# ISS-Notify.net
KiCad netlist of a schematic drawn in EAGLE
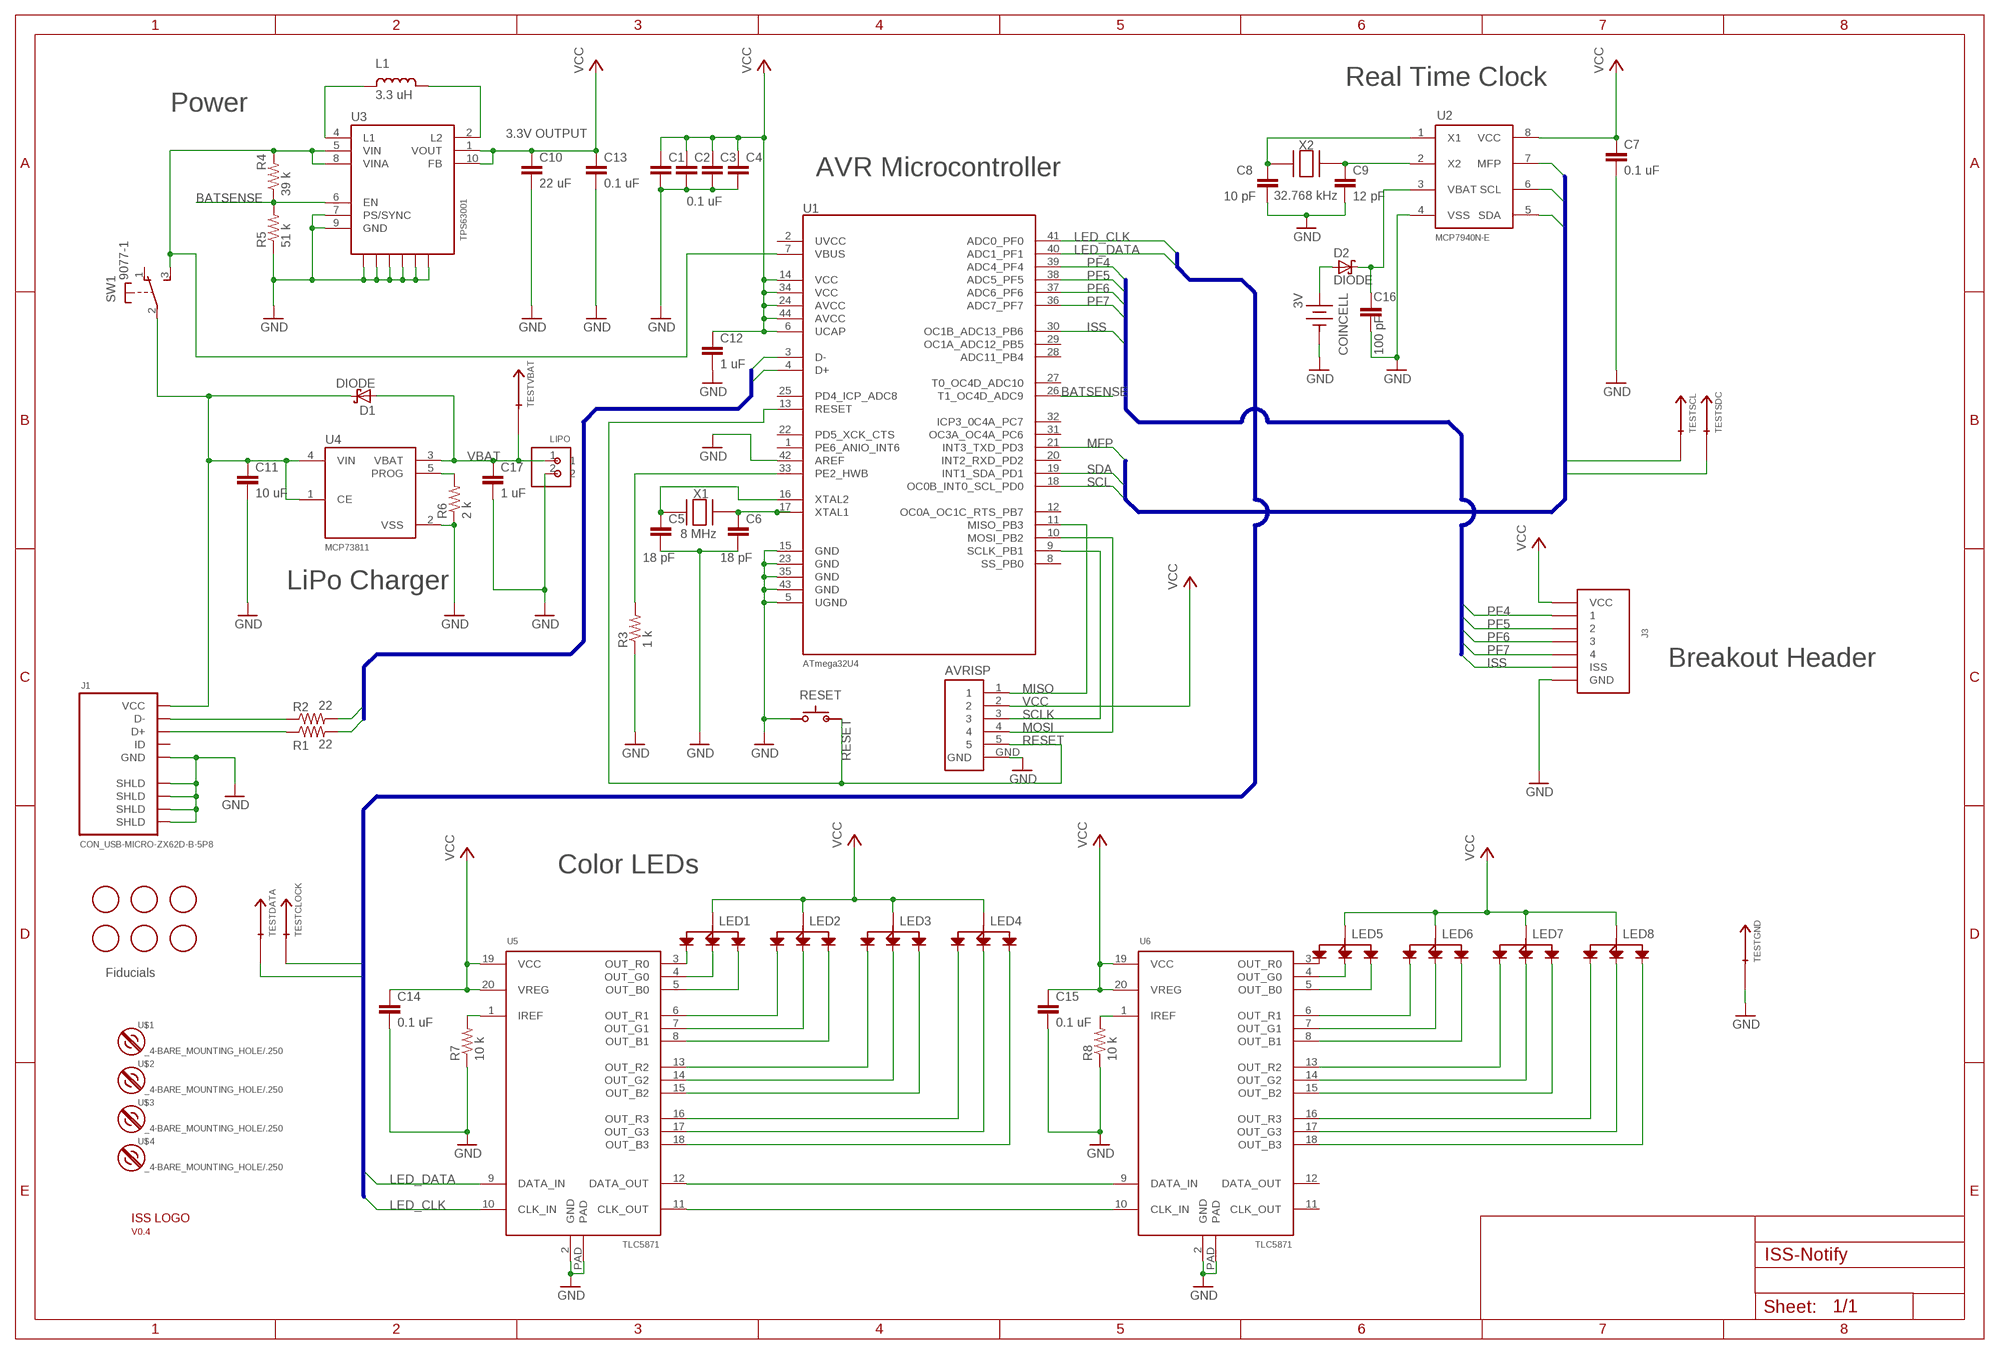
[diagram p0: schematic, sheet 1]

(export (version "E")
  (design (tool "Eeschema 10.0.6"))
  (components
    (comp (ref "AVRISP")
      (value "AVRISP")
      (footprint "eagle-import:AVRISP")
      (libsource (lib "eagle-import") (part "AVRISP"))
    )
    (comp (ref "C1")
      (value "0.1 uF")
      (footprint "eagle-import:0603-C-NOSILK")
      (libsource (lib "eagle-import") (part "C-EU0603-C-NOSILK"))
    )
    (comp (ref "C2")
      (value "0.1 uF")
      (footprint "eagle-import:0603-C-NOSILK")
      (libsource (lib "eagle-import") (part "C-EU0603-C-NOSILK"))
    )
    (comp (ref "C3")
      (value "0.1 uF")
      (footprint "eagle-import:0603-C-NOSILK")
      (libsource (lib "eagle-import") (part "C-EU0603-C-NOSILK"))
    )
    (comp (ref "C4")
      (value "0.1 uF")
      (footprint "eagle-import:0603-C-NOSILK")
      (libsource (lib "eagle-import") (part "C-EU0603-C-NOSILK"))
    )
    (comp (ref "C5")
      (value "18 pF")
      (footprint "eagle-import:0603-C-NOSILK")
      (libsource (lib "eagle-import") (part "C-EU0603-C-NOSILK"))
    )
    (comp (ref "C6")
      (value "18 pF")
      (footprint "eagle-import:0603-C-NOSILK")
      (libsource (lib "eagle-import") (part "C-EU0603-C-NOSILK"))
    )
    (comp (ref "C7")
      (value "0.1 uF")
      (footprint "eagle-import:0603-C-NOSILK")
      (libsource (lib "eagle-import") (part "C-EU0603-C-NOSILK"))
    )
    (comp (ref "C8")
      (value "10 pF")
      (footprint "eagle-import:0603-C-NOSILK")
      (libsource (lib "eagle-import") (part "C-EU0603-C-NOSILK"))
    )
    (comp (ref "C9")
      (value "12 pF")
      (footprint "eagle-import:0603-C-NOSILK")
      (libsource (lib "eagle-import") (part "C-EU0603-C-NOSILK"))
    )
    (comp (ref "C10")
      (value "22 uF")
      (footprint "eagle-import:0805-C-NOSILK")
      (libsource (lib "eagle-import") (part "C-EU0805-C-NOSILK"))
    )
    (comp (ref "C11")
      (value "10 uF")
      (footprint "eagle-import:0805-C-NOSILK")
      (libsource (lib "eagle-import") (part "C-EU0805-C-NOSILK"))
    )
    (comp (ref "C12")
      (value "1 uF")
      (footprint "eagle-import:0603-C-NOSILK")
      (libsource (lib "eagle-import") (part "C-EU0603-C-NOSILK"))
    )
    (comp (ref "C13")
      (value "0.1 uF")
      (footprint "eagle-import:0603-C-NOSILK")
      (libsource (lib "eagle-import") (part "C-EU0603-C-NOSILK"))
    )
    (comp (ref "C14")
      (value "0.1 uF")
      (footprint "eagle-import:0603-C-NOSILK")
      (libsource (lib "eagle-import") (part "C-EU0603-C-NOSILK"))
    )
    (comp (ref "C15")
      (value "0.1 uF")
      (footprint "eagle-import:0603-C-NOSILK")
      (libsource (lib "eagle-import") (part "C-EU0603-C-NOSILK"))
    )
    (comp (ref "C16")
      (value "100 pF")
      (footprint "eagle-import:0603-C-NOSILK")
      (libsource (lib "eagle-import") (part "C-EU0603-C-NOSILK"))
    )
    (comp (ref "C17")
      (value "1 uF")
      (footprint "eagle-import:0603-C-NOSILK")
      (libsource (lib "eagle-import") (part "C-EU0603-C-NOSILK"))
    )
    (comp (ref "COINCELL")
      (value "3V")
      (footprint "eagle-import:COINCELL")
      (libsource (lib "eagle-import") (part "COINCELL"))
    )
    (comp (ref "D1")
      (value "DIODE")
      (footprint "eagle-import:0805-DIODE")
      (libsource (lib "eagle-import") (part "DIODE"))
    )
    (comp (ref "D2")
      (value "DIODE")
      (footprint "eagle-import:0805-DIODE")
      (libsource (lib "eagle-import") (part "DIODE"))
    )
    (comp (ref "J1")
      (value "CON_USB-MICRO-ZX62D-B-5P8")
      (footprint "eagle-import:USBMICROSMT-HIROSE")
      (libsource (lib "eagle-import") (part "CON_USB-MICRO-ZX62D-B-5P8"))
    )
    (comp (ref "J3")
      (value "PROTOSPACE2")
      (footprint "eagle-import:PROTOSPACE2")
      (libsource (lib "eagle-import") (part "PROTOSPACE2"))
    )
    (comp (ref "L1")
      (value "3.3 uH")
      (footprint "eagle-import:0805-C-NOSILK")
      (libsource (lib "eagle-import") (part "PWR_INDUCTOR"))
    )
    (comp (ref "LED1")
      (value "RGBLED")
      (footprint "eagle-import:SMDRGBLED")
      (libsource (lib "eagle-import") (part "RGBLED"))
    )
    (comp (ref "LED2")
      (value "RGBLED")
      (footprint "eagle-import:SMDRGBLED")
      (libsource (lib "eagle-import") (part "RGBLED"))
    )
    (comp (ref "LED3")
      (value "RGBLED")
      (footprint "eagle-import:SMDRGBLED")
      (libsource (lib "eagle-import") (part "RGBLED"))
    )
    (comp (ref "LED4")
      (value "RGBLED")
      (footprint "eagle-import:SMDRGBLED")
      (libsource (lib "eagle-import") (part "RGBLED"))
    )
    (comp (ref "LED5")
      (value "RGBLED")
      (footprint "eagle-import:SMDRGBLED")
      (libsource (lib "eagle-import") (part "RGBLED"))
    )
    (comp (ref "LED6")
      (value "RGBLED")
      (footprint "eagle-import:SMDRGBLED")
      (libsource (lib "eagle-import") (part "RGBLED"))
    )
    (comp (ref "LED7")
      (value "RGBLED")
      (footprint "eagle-import:SMDRGBLED")
      (libsource (lib "eagle-import") (part "RGBLED"))
    )
    (comp (ref "LED8")
      (value "RGBLED")
      (footprint "eagle-import:SMDRGBLED")
      (libsource (lib "eagle-import") (part "RGBLED"))
    )
    (comp (ref "LIPO")
      (value "JST2")
      (footprint "eagle-import:JSTHEAD")
      (libsource (lib "eagle-import") (part "JST2"))
    )
    (comp (ref "R1")
      (value "22")
      (footprint "eagle-import:0603-C-NOSILK")
      (libsource (lib "eagle-import") (part "R-US_0603-C-NOSILK"))
    )
    (comp (ref "R2")
      (value "22")
      (footprint "eagle-import:0603-C-NOSILK")
      (libsource (lib "eagle-import") (part "R-US_0603-C-NOSILK"))
    )
    (comp (ref "R3")
      (value "1 k")
      (footprint "eagle-import:0603-C-NOSILK")
      (libsource (lib "eagle-import") (part "R-US_0603-C-NOSILK"))
    )
    (comp (ref "R4")
      (value "39 k")
      (footprint "eagle-import:0603-C-NOSILK")
      (libsource (lib "eagle-import") (part "R-US_0603-C-NOSILK"))
    )
    (comp (ref "R5")
      (value "51 k")
      (footprint "eagle-import:0603-C-NOSILK")
      (libsource (lib "eagle-import") (part "R-US_0603-C-NOSILK"))
    )
    (comp (ref "R6")
      (value "2 k")
      (footprint "eagle-import:0603-C-NOSILK")
      (libsource (lib "eagle-import") (part "R-US_0603-C-NOSILK"))
    )
    (comp (ref "R7")
      (value "10 k")
      (footprint "eagle-import:0603-C-NOSILK")
      (libsource (lib "eagle-import") (part "R-US_0603-C-NOSILK"))
    )
    (comp (ref "R8")
      (value "10 k")
      (footprint "eagle-import:0603-C-NOSILK")
      (libsource (lib "eagle-import") (part "R-US_0603-C-NOSILK"))
    )
    (comp (ref "RESET")
      (value "SWITCH")
      (footprint "eagle-import:SWITCH")
      (libsource (lib "eagle-import") (part "SWITCH"))
    )
    (comp (ref "SW1")
      (value "9077-1")
      (footprint "eagle-import:ESWITCH")
      (libsource (lib "eagle-import") (part "9077-1"))
    )
    (comp (ref "TESTCLOCK")
      (value "TESTPIN")
      (footprint "eagle-import:TESTPIN")
      (libsource (lib "eagle-import") (part "TESTPIN"))
    )
    (comp (ref "TESTDATA")
      (value "TESTPIN")
      (footprint "eagle-import:TESTPIN")
      (libsource (lib "eagle-import") (part "TESTPIN"))
    )
    (comp (ref "TESTGND")
      (value "TESTPIN")
      (footprint "eagle-import:TESTPIN")
      (libsource (lib "eagle-import") (part "TESTPIN"))
    )
    (comp (ref "TESTSCL")
      (value "TESTPIN")
      (footprint "eagle-import:TESTPIN")
      (libsource (lib "eagle-import") (part "TESTPIN"))
    )
    (comp (ref "TESTSDC")
      (value "TESTPIN")
      (footprint "eagle-import:TESTPIN")
      (libsource (lib "eagle-import") (part "TESTPIN"))
    )
    (comp (ref "TESTVBAT")
      (value "TESTPIN")
      (footprint "eagle-import:TESTPIN")
      (libsource (lib "eagle-import") (part "TESTPIN"))
    )
    (comp (ref "U$1")
      (value "_4-BARE_MOUNTING_HOLE/.250")
      (footprint "eagle-import:_4_.250-BARE+STD_WASHER")
      (libsource (lib "eagle-import") (part "_4-BARE_MOUNTING_HOLE/.250"))
    )
    (comp (ref "U$2")
      (value "_4-BARE_MOUNTING_HOLE/.250")
      (footprint "eagle-import:_4_.250-BARE+STD_WASHER")
      (libsource (lib "eagle-import") (part "_4-BARE_MOUNTING_HOLE/.250"))
    )
    (comp (ref "U$3")
      (value "_4-BARE_MOUNTING_HOLE/.250")
      (footprint "eagle-import:_4_.250-BARE+STD_WASHER")
      (libsource (lib "eagle-import") (part "_4-BARE_MOUNTING_HOLE/.250"))
    )
    (comp (ref "U$4")
      (value "_4-BARE_MOUNTING_HOLE/.250")
      (footprint "eagle-import:_4_.250-BARE+STD_WASHER")
      (libsource (lib "eagle-import") (part "_4-BARE_MOUNTING_HOLE/.250"))
    )
    (comp (ref "U$5")
      (value "V0.4")
      (footprint "eagle-import:LOGO")
      (libsource (lib "eagle-import") (part "LOGO"))
    )
    (comp (ref "U$6")
      (value "FIDUCIAL")
      (footprint "eagle-import:FIDUCIAL_1MM")
      (libsource (lib "eagle-import") (part "FIDUCIAL"))
    )
    (comp (ref "U$7")
      (value "FIDUCIAL")
      (footprint "eagle-import:FIDUCIAL_1MM")
      (libsource (lib "eagle-import") (part "FIDUCIAL"))
    )
    (comp (ref "U$8")
      (value "FIDUCIAL")
      (footprint "eagle-import:FIDUCIAL_1MM")
      (libsource (lib "eagle-import") (part "FIDUCIAL"))
    )
    (comp (ref "U$9")
      (value "FIDUCIAL")
      (footprint "eagle-import:FIDUCIAL_1MM")
      (libsource (lib "eagle-import") (part "FIDUCIAL"))
    )
    (comp (ref "U$10")
      (value "FIDUCIAL")
      (footprint "eagle-import:FIDUCIAL_1MM")
      (libsource (lib "eagle-import") (part "FIDUCIAL"))
    )
    (comp (ref "U$11")
      (value "FIDUCIAL")
      (footprint "eagle-import:FIDUCIAL_1MM")
      (libsource (lib "eagle-import") (part "FIDUCIAL"))
    )
    (comp (ref "U1")
      (value "ATMEGA32U4")
      (footprint "eagle-import:TQFP-44")
      (libsource (lib "eagle-import") (part "ATMEGA32U4"))
    )
    (comp (ref "U2")
      (value "MCP7940N")
      (footprint "eagle-import:MCP7940N")
      (libsource (lib "eagle-import") (part "MCP7940N"))
    )
    (comp (ref "U3")
      (value "TPS63001")
      (footprint "eagle-import:QFN10")
      (libsource (lib "eagle-import") (part "TPS63001"))
    )
    (comp (ref "U4")
      (value "MCP73811")
      (footprint "eagle-import:SOT23-5L")
      (libsource (lib "eagle-import") (part "MCP73811"))
    )
    (comp (ref "U5")
      (value "TLC5971")
      (footprint "eagle-import:R-PDSO-G20")
      (libsource (lib "eagle-import") (part "TLC5971"))
    )
    (comp (ref "U6")
      (value "TLC5971")
      (footprint "eagle-import:R-PDSO-G20")
      (libsource (lib "eagle-import") (part "TLC5971"))
    )
    (comp (ref "X1")
      (value "8 MHz")
      (footprint "eagle-import:CX5Z")
      (libsource (lib "eagle-import") (part "CX5Z"))
    )
    (comp (ref "X2")
      (value "32.768 kHz")
      (footprint "eagle-import:ABS10")
      (libsource (lib "eagle-import") (part "ABS10"))
    )
  )
  (nets
    (net (code "1") (name "/BATSENSE") (class "Default")
      (node (ref "R4") (pin "1") (pinfunction "1_1") (pintype "passive"))
      (node (ref "R5") (pin "2") (pinfunction "2_2") (pintype "passive"))
      (node (ref "U1") (pin "26") (pinfunction "T1_OC4D_ADC9_26") (pintype "bidirectional"))
      (node (ref "U3") (pin "6") (pinfunction "EN_6") (pintype "bidirectional"))
    )
    (net (code "2") (name "/D+") (class "Default")
      (node (ref "R1") (pin "2") (pinfunction "2_2") (pintype "passive"))
      (node (ref "U1") (pin "4") (pinfunction "D+_4") (pintype "bidirectional"))
    )
    (net (code "3") (name "/D-") (class "Default")
      (node (ref "R2") (pin "2") (pinfunction "2_2") (pintype "passive"))
      (node (ref "U1") (pin "3") (pinfunction "D-_3") (pintype "bidirectional"))
    )
    (net (code "4") (name "/ISS") (class "Default")
      (node (ref "J3") (pin "ISS") (pinfunction "ISS_ISS") (pintype "bidirectional"))
      (node (ref "U1") (pin "30") (pinfunction "OC1B_ADC13_PB6_30") (pintype "bidirectional"))
    )
    (net (code "5") (name "/LED_CLK") (class "Default")
      (node (ref "TESTCLOCK") (pin "P$1") (pinfunction "TEST_P$1") (pintype "bidirectional"))
      (node (ref "U1") (pin "41") (pinfunction "ADC0_PF0_41") (pintype "bidirectional"))
      (node (ref "U5") (pin "10") (pinfunction "CLK_IN_10") (pintype "bidirectional"))
    )
    (net (code "6") (name "/LED_DATA") (class "Default")
      (node (ref "TESTDATA") (pin "P$1") (pinfunction "TEST_P$1") (pintype "bidirectional"))
      (node (ref "U1") (pin "40") (pinfunction "ADC1_PF1_40") (pintype "bidirectional"))
      (node (ref "U5") (pin "9") (pinfunction "DATA_IN_9") (pintype "bidirectional"))
    )
    (net (code "7") (name "/MFP") (class "Default")
      (node (ref "U1") (pin "21") (pinfunction "INT3_TXD_PD3_21") (pintype "bidirectional"))
      (node (ref "U2") (pin "7") (pinfunction "MFP_7") (pintype "bidirectional"))
    )
    (net (code "8") (name "/MISO") (class "Default")
      (node (ref "AVRISP") (pin "1") (pinfunction "1_1") (pintype "bidirectional"))
      (node (ref "U1") (pin "11") (pinfunction "MISO_PB3_11") (pintype "bidirectional"))
    )
    (net (code "9") (name "/MOSI") (class "Default")
      (node (ref "AVRISP") (pin "4") (pinfunction "4_4") (pintype "bidirectional"))
      (node (ref "U1") (pin "10") (pinfunction "MOSI_PB2_10") (pintype "bidirectional"))
    )
    (net (code "10") (name "/PF4") (class "Default")
      (node (ref "J3") (pin "1") (pinfunction "1_1") (pintype "bidirectional"))
      (node (ref "U1") (pin "39") (pinfunction "ADC4_PF4_39") (pintype "bidirectional"))
    )
    (net (code "11") (name "/PF5") (class "Default")
      (node (ref "J3") (pin "2") (pinfunction "2_2") (pintype "bidirectional"))
      (node (ref "U1") (pin "38") (pinfunction "ADC5_PF5_38") (pintype "bidirectional"))
    )
    (net (code "12") (name "/PF6") (class "Default")
      (node (ref "J3") (pin "3") (pinfunction "3_3") (pintype "bidirectional"))
      (node (ref "U1") (pin "37") (pinfunction "ADC6_PF6_37") (pintype "bidirectional"))
    )
    (net (code "13") (name "/PF7") (class "Default")
      (node (ref "J3") (pin "4") (pinfunction "4_4") (pintype "bidirectional"))
      (node (ref "U1") (pin "36") (pinfunction "ADC7_PF7_36") (pintype "bidirectional"))
    )
    (net (code "14") (name "/RESET") (class "Default")
      (node (ref "AVRISP") (pin "5") (pinfunction "5_5") (pintype "bidirectional"))
      (node (ref "RESET") (pin "1") (pinfunction "1_1") (pintype "bidirectional"))
      (node (ref "U1") (pin "13") (pinfunction "RESET_13") (pintype "input"))
    )
    (net (code "15") (name "/SCL") (class "Default")
      (node (ref "TESTSCL") (pin "P$1") (pinfunction "TEST_P$1") (pintype "bidirectional"))
      (node (ref "U1") (pin "18") (pinfunction "OC0B_INT0_SCL_PD0_18") (pintype "bidirectional"))
      (node (ref "U2") (pin "6") (pinfunction "SCL_6") (pintype "bidirectional"))
    )
    (net (code "16") (name "/SCLK") (class "Default")
      (node (ref "AVRISP") (pin "3") (pinfunction "3_3") (pintype "bidirectional"))
      (node (ref "U1") (pin "9") (pinfunction "SCLK_PB1_9") (pintype "bidirectional"))
    )
    (net (code "17") (name "/SDA") (class "Default")
      (node (ref "TESTSDC") (pin "P$1") (pinfunction "TEST_P$1") (pintype "bidirectional"))
      (node (ref "U1") (pin "19") (pinfunction "INT1_SDA_PD1_19") (pintype "bidirectional"))
      (node (ref "U2") (pin "5") (pinfunction "SDA_5") (pintype "bidirectional"))
    )
    (net (code "18") (name "/UVCC") (class "Default")
      (node (ref "U1") (pin "2") (pinfunction "UVCC_2") (pintype "power_in"))
    )
    (net (code "19") (name "/VBAT") (class "Default")
      (node (ref "C17") (pin "1") (pinfunction "1_1") (pintype "passive"))
      (node (ref "D1") (pin "A") (pinfunction "A_A") (pintype "passive"))
      (node (ref "LIPO") (pin "1") (pinfunction "1_1") (pintype "bidirectional"))
      (node (ref "TESTVBAT") (pin "P$1") (pinfunction "TEST_P$1") (pintype "bidirectional"))
      (node (ref "U4") (pin "3") (pinfunction "VBAT_3") (pintype "bidirectional"))
    )
    (net (code "21") (name "GND") (class "Default")
      (node (ref "AVRISP") (pin "GND") (pinfunction "GND_GND") (pintype "power_in"))
      (node (ref "C1") (pin "2") (pinfunction "2_2") (pintype "passive"))
      (node (ref "C10") (pin "2") (pinfunction "2_2") (pintype "passive"))
      (node (ref "C11") (pin "2") (pinfunction "2_2") (pintype "passive"))
      (node (ref "C12") (pin "2") (pinfunction "2_2") (pintype "passive"))
      (node (ref "C13") (pin "2") (pinfunction "2_2") (pintype "passive"))
      (node (ref "C14") (pin "2") (pinfunction "2_2") (pintype "passive"))
      (node (ref "C15") (pin "2") (pinfunction "2_2") (pintype "passive"))
      (node (ref "C16") (pin "2") (pinfunction "2_2") (pintype "passive"))
      (node (ref "C17") (pin "2") (pinfunction "2_2") (pintype "passive"))
      (node (ref "C2") (pin "2") (pinfunction "2_2") (pintype "passive"))
      (node (ref "C3") (pin "2") (pinfunction "2_2") (pintype "passive"))
      (node (ref "C4") (pin "2") (pinfunction "2_2") (pintype "passive"))
      (node (ref "C5") (pin "2") (pinfunction "2_2") (pintype "passive"))
      (node (ref "C6") (pin "2") (pinfunction "2_2") (pintype "passive"))
      (node (ref "C7") (pin "2") (pinfunction "2_2") (pintype "passive"))
      (node (ref "C8") (pin "2") (pinfunction "2_2") (pintype "passive"))
      (node (ref "C9") (pin "2") (pinfunction "2_2") (pintype "passive"))
      (node (ref "COINCELL") (pin "GND") (pinfunction "GND_GND") (pintype "bidirectional"))
      (node (ref "J1") (pin "P$1") (pinfunction "SHLD_P$1") (pintype "power_in"))
      (node (ref "J1") (pin "P$2") (pinfunction "SHLD_P$2") (pintype "power_in"))
      (node (ref "J1") (pin "P$3") (pinfunction "SHLD_P$3") (pintype "power_in"))
      (node (ref "J1") (pin "P$4") (pinfunction "SHLD_P$4") (pintype "power_in"))
      (node (ref "J1") (pin "P5") (pinfunction "GND_P5") (pintype "power_in"))
      (node (ref "J3") (pin "GND") (pinfunction "GND_GND") (pintype "bidirectional"))
      (node (ref "LIPO") (pin "2") (pinfunction "2_2") (pintype "bidirectional"))
      (node (ref "R3") (pin "1") (pinfunction "1_1") (pintype "passive"))
      (node (ref "R5") (pin "1") (pinfunction "1_1") (pintype "passive"))
      (node (ref "R6") (pin "1") (pinfunction "1_1") (pintype "passive"))
      (node (ref "R7") (pin "1") (pinfunction "1_1") (pintype "passive"))
      (node (ref "R8") (pin "1") (pinfunction "1_1") (pintype "passive"))
      (node (ref "RESET") (pin "3") (pinfunction "2_3") (pintype "bidirectional"))
      (node (ref "TESTGND") (pin "P$1") (pinfunction "TEST_P$1") (pintype "bidirectional"))
      (node (ref "U1") (pin "15") (pinfunction "GND_15") (pintype "power_in"))
      (node (ref "U1") (pin "23") (pinfunction "GND_23") (pintype "power_in"))
      (node (ref "U1") (pin "35") (pinfunction "GND_35") (pintype "power_in"))
      (node (ref "U1") (pin "42") (pinfunction "AREF_42") (pintype "input"))
      (node (ref "U1") (pin "43") (pinfunction "GND_43") (pintype "power_in"))
      (node (ref "U1") (pin "5") (pinfunction "UGND_5") (pintype "power_in"))
      (node (ref "U2") (pin "4") (pinfunction "VSS_4") (pintype "bidirectional"))
      (node (ref "U3") (pin "3") (pinfunction "PGND_3") (pintype "bidirectional"))
      (node (ref "U3") (pin "7") (pinfunction "PS/SYNC_7") (pintype "bidirectional"))
      (node (ref "U3") (pin "9") (pinfunction "GND_9") (pintype "bidirectional"))
      (node (ref "U3") (pin "PAD") (pinfunction "GNDPAD_PAD") (pintype "bidirectional"))
      (node (ref "U3") (pin "PGND1") (pinfunction "PGND1_PGND1") (pintype "bidirectional"))
      (node (ref "U3") (pin "PGND2") (pinfunction "PGND2_PGND2") (pintype "bidirectional"))
      (node (ref "U3") (pin "PGND3") (pinfunction "PGND3_PGND3") (pintype "bidirectional"))
      (node (ref "U3") (pin "PGND4") (pinfunction "PGND4_PGND4") (pintype "bidirectional"))
      (node (ref "U4") (pin "2") (pinfunction "VSS_2") (pintype "bidirectional"))
      (node (ref "U5") (pin "2") (pinfunction "GND_2") (pintype "bidirectional"))
      (node (ref "U5") (pin "PAD") (pinfunction "PAD_PAD") (pintype "bidirectional"))
      (node (ref "U6") (pin "2") (pinfunction "GND_2") (pintype "bidirectional"))
      (node (ref "U6") (pin "PAD") (pinfunction "PAD_PAD") (pintype "bidirectional"))
    )
    (net (code "22") (name "Net-(COINCELL-VBAT)") (class "Default")
      (node (ref "COINCELL") (pin "POS1") (pinfunction "VBAT_POS1") (pintype "bidirectional"))
      (node (ref "D2") (pin "A") (pinfunction "A_A") (pintype "passive"))
    )
    (net (code "23") (name "Net-(J1-D+)") (class "Default")
      (node (ref "J1") (pin "P3") (pinfunction "D+_P3") (pintype "bidirectional"))
      (node (ref "R1") (pin "1") (pinfunction "1_1") (pintype "passive"))
    )
    (net (code "24") (name "Net-(J1-D-)") (class "Default")
      (node (ref "J1") (pin "P2") (pinfunction "D-_P2") (pintype "bidirectional"))
      (node (ref "R2") (pin "1") (pinfunction "1_1") (pintype "passive"))
    )
    (net (code "25") (name "Net-(J1-VCC)") (class "Default")
      (node (ref "C11") (pin "1") (pinfunction "1_1") (pintype "passive"))
      (node (ref "D1") (pin "C") (pinfunction "C_C") (pintype "passive"))
      (node (ref "J1") (pin "P1") (pinfunction "VCC_P1") (pintype "power_in"))
      (node (ref "SW1") (pin "2") (pinfunction "P_2") (pintype "passive"))
      (node (ref "U4") (pin "1") (pinfunction "CE_1") (pintype "bidirectional"))
      (node (ref "U4") (pin "4") (pinfunction "VIN_4") (pintype "bidirectional"))
    )
    (net (code "26") (name "Net-(L1-A)") (class "Default")
      (node (ref "L1") (pin "1") (pinfunction "A_1") (pintype "bidirectional"))
      (node (ref "U3") (pin "4") (pinfunction "L1_4") (pintype "bidirectional"))
    )
    (net (code "27") (name "Net-(L1-C)") (class "Default")
      (node (ref "L1") (pin "2") (pinfunction "C_2") (pintype "bidirectional"))
      (node (ref "U3") (pin "2") (pinfunction "L2_2") (pintype "bidirectional"))
    )
    (net (code "28") (name "Net-(LED1-B)") (class "Default")
      (node (ref "LED1") (pin "BLUE") (pinfunction "B_BLUE") (pintype "bidirectional"))
      (node (ref "U5") (pin "5") (pinfunction "OUT_B0_5") (pintype "bidirectional"))
    )
    (net (code "29") (name "Net-(LED1-G)") (class "Default")
      (node (ref "LED1") (pin "GREEN") (pinfunction "G_GREEN") (pintype "bidirectional"))
      (node (ref "U5") (pin "4") (pinfunction "OUT_G0_4") (pintype "bidirectional"))
    )
    (net (code "30") (name "Net-(LED1-R)") (class "Default")
      (node (ref "LED1") (pin "RED") (pinfunction "R_RED") (pintype "bidirectional"))
      (node (ref "U5") (pin "3") (pinfunction "OUT_R0_3") (pintype "bidirectional"))
    )
    (net (code "31") (name "Net-(LED2-B)") (class "Default")
      (node (ref "LED2") (pin "BLUE") (pinfunction "B_BLUE") (pintype "bidirectional"))
      (node (ref "U5") (pin "8") (pinfunction "OUT_B1_8") (pintype "bidirectional"))
    )
    (net (code "32") (name "Net-(LED2-G)") (class "Default")
      (node (ref "LED2") (pin "GREEN") (pinfunction "G_GREEN") (pintype "bidirectional"))
      (node (ref "U5") (pin "7") (pinfunction "OUT_G1_7") (pintype "bidirectional"))
    )
    (net (code "33") (name "Net-(LED2-R)") (class "Default")
      (node (ref "LED2") (pin "RED") (pinfunction "R_RED") (pintype "bidirectional"))
      (node (ref "U5") (pin "6") (pinfunction "OUT_R1_6") (pintype "bidirectional"))
    )
    (net (code "34") (name "Net-(LED3-B)") (class "Default")
      (node (ref "LED3") (pin "BLUE") (pinfunction "B_BLUE") (pintype "bidirectional"))
      (node (ref "U5") (pin "15") (pinfunction "OUT_B2_15") (pintype "bidirectional"))
    )
    (net (code "35") (name "Net-(LED3-G)") (class "Default")
      (node (ref "LED3") (pin "GREEN") (pinfunction "G_GREEN") (pintype "bidirectional"))
      (node (ref "U5") (pin "14") (pinfunction "OUT_G2_14") (pintype "bidirectional"))
    )
    (net (code "36") (name "Net-(LED3-R)") (class "Default")
      (node (ref "LED3") (pin "RED") (pinfunction "R_RED") (pintype "bidirectional"))
      (node (ref "U5") (pin "13") (pinfunction "OUT_R2_13") (pintype "bidirectional"))
    )
    (net (code "37") (name "Net-(LED4-B)") (class "Default")
      (node (ref "LED4") (pin "BLUE") (pinfunction "B_BLUE") (pintype "bidirectional"))
      (node (ref "U5") (pin "18") (pinfunction "OUT_B3_18") (pintype "bidirectional"))
    )
    (net (code "38") (name "Net-(LED4-G)") (class "Default")
      (node (ref "LED4") (pin "GREEN") (pinfunction "G_GREEN") (pintype "bidirectional"))
      (node (ref "U5") (pin "17") (pinfunction "OUT_G3_17") (pintype "bidirectional"))
    )
    (net (code "39") (name "Net-(LED4-R)") (class "Default")
      (node (ref "LED4") (pin "RED") (pinfunction "R_RED") (pintype "bidirectional"))
      (node (ref "U5") (pin "16") (pinfunction "OUT_R3_16") (pintype "bidirectional"))
    )
    (net (code "40") (name "Net-(LED5-B)") (class "Default")
      (node (ref "LED5") (pin "BLUE") (pinfunction "B_BLUE") (pintype "bidirectional"))
      (node (ref "U6") (pin "5") (pinfunction "OUT_B0_5") (pintype "bidirectional"))
    )
    (net (code "41") (name "Net-(LED5-G)") (class "Default")
      (node (ref "LED5") (pin "GREEN") (pinfunction "G_GREEN") (pintype "bidirectional"))
      (node (ref "U6") (pin "4") (pinfunction "OUT_G0_4") (pintype "bidirectional"))
    )
    (net (code "42") (name "Net-(LED5-R)") (class "Default")
      (node (ref "LED5") (pin "RED") (pinfunction "R_RED") (pintype "bidirectional"))
      (node (ref "U6") (pin "3") (pinfunction "OUT_R0_3") (pintype "bidirectional"))
    )
    (net (code "43") (name "Net-(LED6-B)") (class "Default")
      (node (ref "LED6") (pin "BLUE") (pinfunction "B_BLUE") (pintype "bidirectional"))
      (node (ref "U6") (pin "8") (pinfunction "OUT_B1_8") (pintype "bidirectional"))
    )
    (net (code "44") (name "Net-(LED6-G)") (class "Default")
      (node (ref "LED6") (pin "GREEN") (pinfunction "G_GREEN") (pintype "bidirectional"))
      (node (ref "U6") (pin "7") (pinfunction "OUT_G1_7") (pintype "bidirectional"))
    )
    (net (code "45") (name "Net-(LED6-R)") (class "Default")
      (node (ref "LED6") (pin "RED") (pinfunction "R_RED") (pintype "bidirectional"))
      (node (ref "U6") (pin "6") (pinfunction "OUT_R1_6") (pintype "bidirectional"))
    )
    (net (code "46") (name "Net-(LED7-B)") (class "Default")
      (node (ref "LED7") (pin "BLUE") (pinfunction "B_BLUE") (pintype "bidirectional"))
      (node (ref "U6") (pin "15") (pinfunction "OUT_B2_15") (pintype "bidirectional"))
    )
    (net (code "47") (name "Net-(LED7-G)") (class "Default")
      (node (ref "LED7") (pin "GREEN") (pinfunction "G_GREEN") (pintype "bidirectional"))
      (node (ref "U6") (pin "14") (pinfunction "OUT_G2_14") (pintype "bidirectional"))
    )
    (net (code "48") (name "Net-(LED7-R)") (class "Default")
      (node (ref "LED7") (pin "RED") (pinfunction "R_RED") (pintype "bidirectional"))
      (node (ref "U6") (pin "13") (pinfunction "OUT_R2_13") (pintype "bidirectional"))
    )
    (net (code "49") (name "Net-(LED8-B)") (class "Default")
      (node (ref "LED8") (pin "BLUE") (pinfunction "B_BLUE") (pintype "bidirectional"))
      (node (ref "U6") (pin "18") (pinfunction "OUT_B3_18") (pintype "bidirectional"))
    )
    (net (code "50") (name "Net-(LED8-G)") (class "Default")
      (node (ref "LED8") (pin "GREEN") (pinfunction "G_GREEN") (pintype "bidirectional"))
      (node (ref "U6") (pin "17") (pinfunction "OUT_G3_17") (pintype "bidirectional"))
    )
    (net (code "51") (name "Net-(LED8-R)") (class "Default")
      (node (ref "LED8") (pin "RED") (pinfunction "R_RED") (pintype "bidirectional"))
      (node (ref "U6") (pin "16") (pinfunction "OUT_R3_16") (pintype "bidirectional"))
    )
    (net (code "52") (name "Net-(SW1-S)") (class "Default")
      (node (ref "R4") (pin "2") (pinfunction "2_2") (pintype "passive"))
      (node (ref "SW1") (pin "3") (pinfunction "S_3") (pintype "passive"))
      (node (ref "U1") (pin "7") (pinfunction "VBUS_7") (pintype "bidirectional"))
      (node (ref "U3") (pin "5") (pinfunction "VIN_5") (pintype "bidirectional"))
      (node (ref "U3") (pin "8") (pinfunction "VINA_8") (pintype "bidirectional"))
    )
    (net (code "53") (name "Net-(U1-PE2_HWB)") (class "Default")
      (node (ref "R3") (pin "2") (pinfunction "2_2") (pintype "passive"))
      (node (ref "U1") (pin "33") (pinfunction "PE2_HWB_33") (pintype "bidirectional"))
    )
    (net (code "54") (name "Net-(U1-XTAL1)") (class "Default")
      (node (ref "C6") (pin "1") (pinfunction "1_1") (pintype "passive"))
      (node (ref "U1") (pin "17") (pinfunction "XTAL1_17") (pintype "tri_state"))
      (node (ref "X1") (pin "3") (pinfunction "2_3") (pintype "bidirectional"))
    )
    (net (code "55") (name "Net-(U1-XTAL2)") (class "Default")
      (node (ref "C5") (pin "1") (pinfunction "1_1") (pintype "passive"))
      (node (ref "U1") (pin "16") (pinfunction "XTAL2_16") (pintype "tri_state"))
      (node (ref "X1") (pin "1") (pinfunction "1_1") (pintype "bidirectional"))
    )
    (net (code "56") (name "Net-(U2-VBAT)") (class "Default")
      (node (ref "C16") (pin "1") (pinfunction "1_1") (pintype "passive"))
      (node (ref "D2") (pin "C") (pinfunction "C_C") (pintype "passive"))
      (node (ref "U2") (pin "3") (pinfunction "VBAT_3") (pintype "bidirectional"))
    )
    (net (code "57") (name "Net-(U2-X1)") (class "Default")
      (node (ref "C8") (pin "1") (pinfunction "1_1") (pintype "passive"))
      (node (ref "U2") (pin "1") (pinfunction "X1_1") (pintype "bidirectional"))
      (node (ref "X2") (pin "1") (pinfunction "1_1") (pintype "bidirectional"))
    )
    (net (code "58") (name "Net-(U2-X2)") (class "Default")
      (node (ref "C9") (pin "1") (pinfunction "1_1") (pintype "passive"))
      (node (ref "U2") (pin "2") (pinfunction "X2_2") (pintype "bidirectional"))
      (node (ref "X2") (pin "@1") (pinfunction "2_@1") (pintype "bidirectional"))
    )
    (net (code "59") (name "Net-(U4-PROG)") (class "Default")
      (node (ref "R6") (pin "2") (pinfunction "2_2") (pintype "passive"))
      (node (ref "U4") (pin "5") (pinfunction "PROG_5") (pintype "bidirectional"))
    )
    (net (code "60") (name "Net-(U5-CLK_OUT)") (class "Default")
      (node (ref "U5") (pin "11") (pinfunction "CLK_OUT_11") (pintype "bidirectional"))
      (node (ref "U6") (pin "10") (pinfunction "CLK_IN_10") (pintype "bidirectional"))
    )
    (net (code "61") (name "Net-(U5-DATA_OUT)") (class "Default")
      (node (ref "U5") (pin "12") (pinfunction "DATA_OUT_12") (pintype "bidirectional"))
      (node (ref "U6") (pin "9") (pinfunction "DATA_IN_9") (pintype "bidirectional"))
    )
    (net (code "62") (name "Net-(U5-IREF)") (class "Default")
      (node (ref "R7") (pin "2") (pinfunction "2_2") (pintype "passive"))
      (node (ref "U5") (pin "1") (pinfunction "IREF_1") (pintype "bidirectional"))
    )
    (net (code "63") (name "Net-(U6-IREF)") (class "Default")
      (node (ref "R8") (pin "2") (pinfunction "2_2") (pintype "passive"))
      (node (ref "U6") (pin "1") (pinfunction "IREF_1") (pintype "bidirectional"))
    )
    (net (code "64") (name "VCC") (class "Default")
      (node (ref "AVRISP") (pin "2") (pinfunction "2_2") (pintype "bidirectional"))
      (node (ref "C1") (pin "1") (pinfunction "1_1") (pintype "passive"))
      (node (ref "C10") (pin "1") (pinfunction "1_1") (pintype "passive"))
      (node (ref "C12") (pin "1") (pinfunction "1_1") (pintype "passive"))
      (node (ref "C13") (pin "1") (pinfunction "1_1") (pintype "passive"))
      (node (ref "C14") (pin "1") (pinfunction "1_1") (pintype "passive"))
      (node (ref "C15") (pin "1") (pinfunction "1_1") (pintype "passive"))
      (node (ref "C2") (pin "1") (pinfunction "1_1") (pintype "passive"))
      (node (ref "C3") (pin "1") (pinfunction "1_1") (pintype "passive"))
      (node (ref "C4") (pin "1") (pinfunction "1_1") (pintype "passive"))
      (node (ref "C7") (pin "1") (pinfunction "1_1") (pintype "passive"))
      (node (ref "J3") (pin "VCC") (pinfunction "VCC_VCC") (pintype "bidirectional"))
      (node (ref "LED1") (pin "ANODE") (pinfunction "ANODE_ANODE") (pintype "bidirectional"))
      (node (ref "LED2") (pin "ANODE") (pinfunction "ANODE_ANODE") (pintype "bidirectional"))
      (node (ref "LED3") (pin "ANODE") (pinfunction "ANODE_ANODE") (pintype "bidirectional"))
      (node (ref "LED4") (pin "ANODE") (pinfunction "ANODE_ANODE") (pintype "bidirectional"))
      (node (ref "LED5") (pin "ANODE") (pinfunction "ANODE_ANODE") (pintype "bidirectional"))
      (node (ref "LED6") (pin "ANODE") (pinfunction "ANODE_ANODE") (pintype "bidirectional"))
      (node (ref "LED7") (pin "ANODE") (pinfunction "ANODE_ANODE") (pintype "bidirectional"))
      (node (ref "LED8") (pin "ANODE") (pinfunction "ANODE_ANODE") (pintype "bidirectional"))
      (node (ref "U1") (pin "14") (pinfunction "VCC_14") (pintype "power_in"))
      (node (ref "U1") (pin "24") (pinfunction "AVCC_24") (pintype "power_in"))
      (node (ref "U1") (pin "34") (pinfunction "VCC_34") (pintype "power_in"))
      (node (ref "U1") (pin "44") (pinfunction "AVCC_44") (pintype "power_in"))
      (node (ref "U1") (pin "6") (pinfunction "UCAP_6") (pintype "bidirectional"))
      (node (ref "U2") (pin "8") (pinfunction "VCC_8") (pintype "bidirectional"))
      (node (ref "U3") (pin "1") (pinfunction "VOUT_1") (pintype "bidirectional"))
      (node (ref "U3") (pin "10") (pinfunction "FB_10") (pintype "bidirectional"))
      (node (ref "U5") (pin "19") (pinfunction "VCC_19") (pintype "bidirectional"))
      (node (ref "U5") (pin "20") (pinfunction "VREG_20") (pintype "bidirectional"))
      (node (ref "U6") (pin "19") (pinfunction "VCC_19") (pintype "bidirectional"))
      (node (ref "U6") (pin "20") (pinfunction "VREG_20") (pintype "bidirectional"))
    )
    (net (code "65") (name "unconnected-(J1-ID-PadP4)") (class "Default")
      (node (ref "J1") (pin "P4") (pinfunction "ID_P4") (pintype "bidirectional"))
    )
    (net (code "66") (name "unconnected-(SW1-O-Pad1)") (class "Default")
      (node (ref "SW1") (pin "1") (pinfunction "O_1") (pintype "passive"))
    )
    (net (code "67") (name "unconnected-(U1-ADC11_PB4-Pad28)") (class "Default")
      (node (ref "U1") (pin "28") (pinfunction "ADC11_PB4_28") (pintype "bidirectional"))
    )
    (net (code "68") (name "unconnected-(U1-ICP3_0C4A_PC7-Pad32)") (class "Default")
      (node (ref "U1") (pin "32") (pinfunction "ICP3_0C4A_PC7_32") (pintype "bidirectional"))
    )
    (net (code "69") (name "unconnected-(U1-INT2_RXD_PD2-Pad20)") (class "Default")
      (node (ref "U1") (pin "20") (pinfunction "INT2_RXD_PD2_20") (pintype "bidirectional"))
    )
    (net (code "70") (name "unconnected-(U1-OC0A_OC1C_RTS_PB7-Pad12)") (class "Default")
      (node (ref "U1") (pin "12") (pinfunction "OC0A_OC1C_RTS_PB7_12") (pintype "bidirectional"))
    )
    (net (code "71") (name "unconnected-(U1-OC1A_ADC12_PB5-Pad29)") (class "Default")
      (node (ref "U1") (pin "29") (pinfunction "OC1A_ADC12_PB5_29") (pintype "bidirectional"))
    )
    (net (code "72") (name "unconnected-(U1-OC3A_OC4A_PC6-Pad31)") (class "Default")
      (node (ref "U1") (pin "31") (pinfunction "OC3A_OC4A_PC6_31") (pintype "bidirectional"))
    )
    (net (code "73") (name "unconnected-(U1-PD4_ICP_ADC8-Pad25)") (class "Default")
      (node (ref "U1") (pin "25") (pinfunction "PD4_ICP_ADC8_25") (pintype "bidirectional"))
    )
    (net (code "74") (name "unconnected-(U1-PD5_XCK_CTS-Pad22)") (class "Default")
      (node (ref "U1") (pin "22") (pinfunction "PD5_XCK_CTS_22") (pintype "bidirectional"))
    )
    (net (code "75") (name "unconnected-(U1-PE6_ANIO_INT6-Pad1)") (class "Default")
      (node (ref "U1") (pin "1") (pinfunction "PE6_ANIO_INT6_1") (pintype "bidirectional"))
    )
    (net (code "76") (name "unconnected-(U1-SS_PB0-Pad8)") (class "Default")
      (node (ref "U1") (pin "8") (pinfunction "SS_PB0_8") (pintype "bidirectional"))
    )
    (net (code "77") (name "unconnected-(U1-T0_OC4D_ADC10-Pad27)") (class "Default")
      (node (ref "U1") (pin "27") (pinfunction "T0_OC4D_ADC10_27") (pintype "bidirectional"))
    )
    (net (code "78") (name "unconnected-(U6-CLK_OUT-Pad11)") (class "Default")
      (node (ref "U6") (pin "11") (pinfunction "CLK_OUT_11") (pintype "bidirectional"))
    )
    (net (code "79") (name "unconnected-(U6-DATA_OUT-Pad12)") (class "Default")
      (node (ref "U6") (pin "12") (pinfunction "DATA_OUT_12") (pintype "bidirectional"))
    )
  )
)
